# gateway.net
KiCad netlist of a schematic drawn in EAGLE
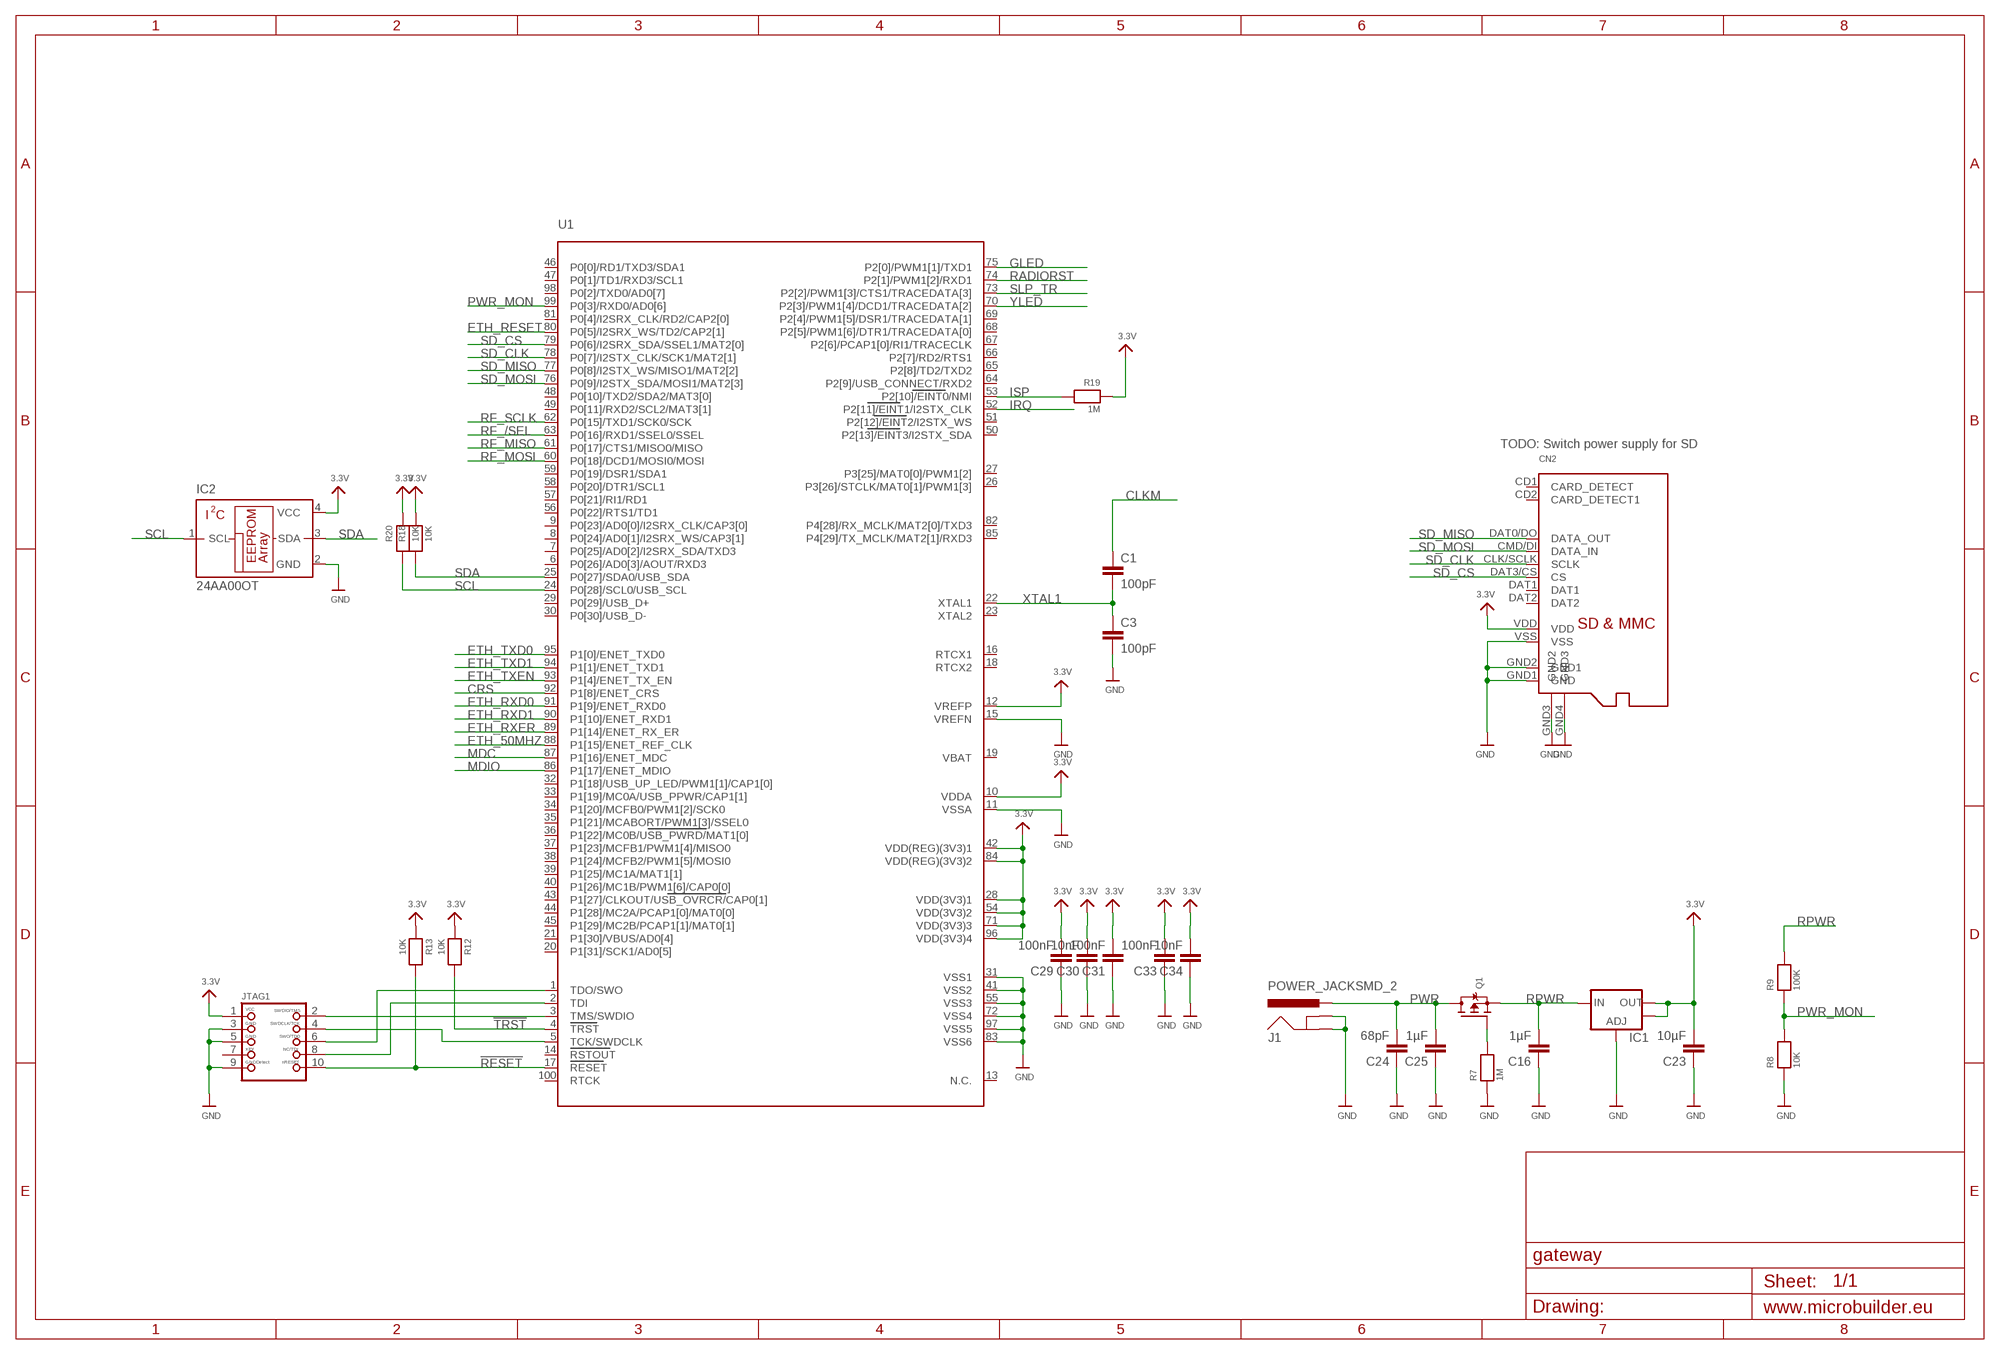
[diagram p0: schematic, sheet 1, part 1 of 2]
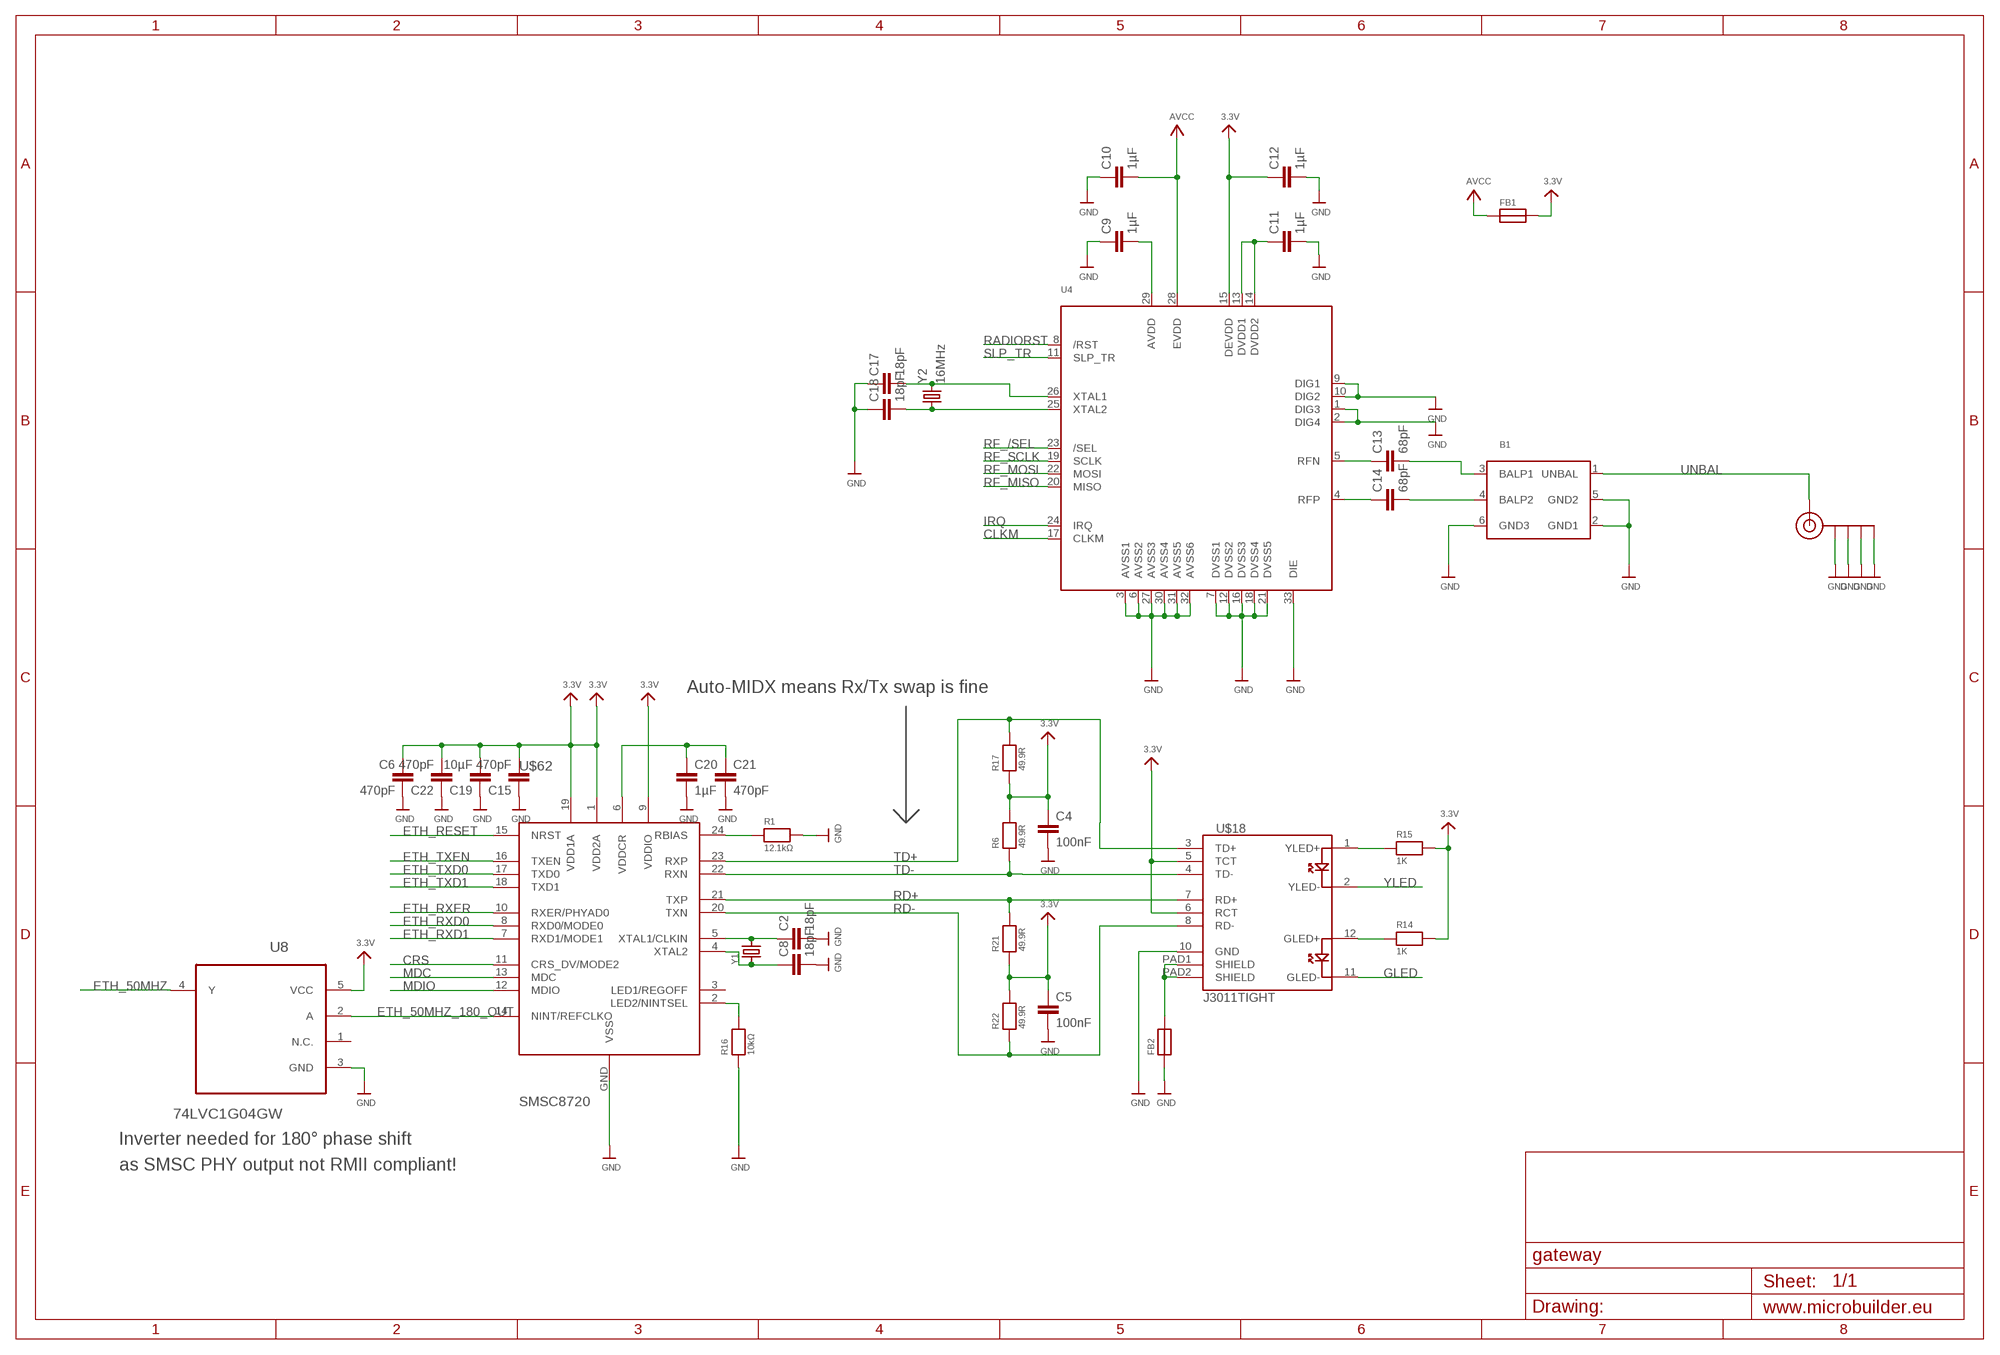
[diagram p1: schematic, sheet 1, part 2 of 2]

(export (version "E")
  (design (tool "Eeschema 10.0.6"))
  (components
    (comp (ref "B1")
      (value "BALUN+LP")
      (footprint "eagle-import:BALUN0805")
      (libsource (lib "eagle-import") (part "BALUN+LP"))
    )
    (comp (ref "C1")
      (value "100pF")
      (footprint "eagle-import:C0603K")
      (libsource (lib "eagle-import") (part "C-EUC0603K"))
    )
    (comp (ref "C2")
      (value "18pF")
      (footprint "eagle-import:C0603K")
      (libsource (lib "eagle-import") (part "C-EUC0603K"))
    )
    (comp (ref "C3")
      (value "100pF")
      (footprint "eagle-import:C0603K")
      (libsource (lib "eagle-import") (part "C-EUC0603K"))
    )
    (comp (ref "C4")
      (value "100nF")
      (footprint "eagle-import:C1206")
      (libsource (lib "eagle-import") (part "C-EUC1206"))
    )
    (comp (ref "C5")
      (value "100nF")
      (footprint "eagle-import:C1206")
      (libsource (lib "eagle-import") (part "C-EUC1206"))
    )
    (comp (ref "C6")
      (value "470pF")
      (footprint "eagle-import:C0603K")
      (libsource (lib "eagle-import") (part "C-EUC0603K"))
    )
    (comp (ref "C8")
      (value "18pF")
      (footprint "eagle-import:C0603K")
      (libsource (lib "eagle-import") (part "C-EUC0603K"))
    )
    (comp (ref "C9")
      (value "1µF")
      (footprint "eagle-import:C0603K")
      (libsource (lib "eagle-import") (part "C-EUC0603K"))
    )
    (comp (ref "C10")
      (value "1µF")
      (footprint "eagle-import:C0603K")
      (libsource (lib "eagle-import") (part "C-EUC0603K"))
    )
    (comp (ref "C11")
      (value "1µF")
      (footprint "eagle-import:C0603K")
      (libsource (lib "eagle-import") (part "C-EUC0603K"))
    )
    (comp (ref "C12")
      (value "1µF")
      (footprint "eagle-import:C0603K")
      (libsource (lib "eagle-import") (part "C-EUC0603K"))
    )
    (comp (ref "C13")
      (value "68pF")
      (footprint "eagle-import:C0603K")
      (libsource (lib "eagle-import") (part "C-EUC0603K"))
    )
    (comp (ref "C14")
      (value "68pF")
      (footprint "eagle-import:C0603K")
      (libsource (lib "eagle-import") (part "C-EUC0603K"))
    )
    (comp (ref "C15")
      (value "470pF")
      (footprint "eagle-import:C0603K")
      (libsource (lib "eagle-import") (part "C-EUC0603K"))
    )
    (comp (ref "C16")
      (value "1µF")
      (footprint "eagle-import:C0603K")
      (libsource (lib "eagle-import") (part "C-EUC0603K"))
    )
    (comp (ref "C17")
      (value "18pF")
      (footprint "eagle-import:C0603K")
      (libsource (lib "eagle-import") (part "C-EUC0603K"))
    )
    (comp (ref "C18")
      (value "18pF")
      (footprint "eagle-import:C0603K")
      (libsource (lib "eagle-import") (part "C-EUC0603K"))
    )
    (comp (ref "C19")
      (value "10µF")
      (footprint "eagle-import:C0603K")
      (libsource (lib "eagle-import") (part "C-EUC0603K"))
    )
    (comp (ref "C20")
      (value "1µF")
      (footprint "eagle-import:C0603K")
      (libsource (lib "eagle-import") (part "C-EUC0603K"))
    )
    (comp (ref "C21")
      (value "470pF")
      (footprint "eagle-import:C0603K")
      (libsource (lib "eagle-import") (part "C-EUC0603K"))
    )
    (comp (ref "C22")
      (value "470pF")
      (footprint "eagle-import:C0603K")
      (libsource (lib "eagle-import") (part "C-EUC0603K"))
    )
    (comp (ref "C23")
      (value "10µF")
      (footprint "eagle-import:C0603K")
      (libsource (lib "eagle-import") (part "C-EUC0603K"))
    )
    (comp (ref "C24")
      (value "68pF")
      (footprint "eagle-import:C0603K")
      (libsource (lib "eagle-import") (part "C-EUC0603K"))
    )
    (comp (ref "C25")
      (value "1µF")
      (footprint "eagle-import:C0603K")
      (libsource (lib "eagle-import") (part "C-EUC0603K"))
    )
    (comp (ref "C29")
      (value "100nF")
      (footprint "eagle-import:C0603K")
      (libsource (lib "eagle-import") (part "C-EUC0603K"))
    )
    (comp (ref "C30")
      (value "10nF")
      (footprint "eagle-import:C0603K")
      (libsource (lib "eagle-import") (part "C-EUC0603K"))
    )
    (comp (ref "C31")
      (value "100nF")
      (footprint "eagle-import:C0603K")
      (libsource (lib "eagle-import") (part "C-EUC0603K"))
    )
    (comp (ref "C33")
      (value "100nF")
      (footprint "eagle-import:C0603K")
      (libsource (lib "eagle-import") (part "C-EUC0603K"))
    )
    (comp (ref "C34")
      (value "10nF")
      (footprint "eagle-import:C0603K")
      (libsource (lib "eagle-import") (part "C-EUC0603K"))
    )
    (comp (ref "CN2")
      (value "MICROSDDM3B")
      (footprint "eagle-import:MICROSD_DM3B")
      (libsource (lib "eagle-import") (part "MICROSDDM3B"))
    )
    (comp (ref "FB1")
      (value "FERRITE")
      (footprint "eagle-import:0603")
      (libsource (lib "eagle-import") (part "FERRITE"))
    )
    (comp (ref "FB2")
      (value "FERRITE")
      (footprint "eagle-import:0603")
      (libsource (lib "eagle-import") (part "FERRITE"))
    )
    (comp (ref "IC1")
      (value "V_REG_LM1117SOT223")
      (footprint "eagle-import:SOT223")
      (libsource (lib "eagle-import") (part "V_REG_LM1117SOT223"))
    )
    (comp (ref "IC2")
      (value "24AA00OT")
      (footprint "eagle-import:SOT23-5L")
      (fields (field (name "MF") "MICROCHIP") (field (name "MPN") "24AA00T-I/OTG"))
      (libsource (lib "eagle-import") (part "2400OTAA"))
    )
    (comp (ref "J$1")
      (value "SMA_EDGE")
      (footprint "eagle-import:SMA-EDGE")
      (libsource (lib "eagle-import") (part "SMA_EDGE"))
    )
    (comp (ref "J1")
      (value "POWER_JACKSMD_2")
      (footprint "eagle-import:POWER_JACK_SMD_2")
      (libsource (lib "eagle-import") (part "POWER_JACKSMD_2"))
    )
    (comp (ref "JTAG1")
      (value "JTAG-CORTEXM3")
      (footprint "eagle-import:2X05_1.27MM_SMT")
      (libsource (lib "eagle-import") (part "JTAG-CORTEXM3"))
    )
    (comp (ref "Q1")
      (value "MOSFET-P")
      (footprint "eagle-import:SOT23-R")
      (libsource (lib "eagle-import") (part "MOSFET-P"))
    )
    (comp (ref "R1")
      (value "12.1kΩ")
      (footprint "eagle-import:0603-MINI")
      (libsource (lib "eagle-import") (part "RESISTOR0603MINI"))
    )
    (comp (ref "R6")
      (value "49.9R")
      (footprint "eagle-import:0603-MINI")
      (libsource (lib "eagle-import") (part "RESISTOR0603MINI"))
    )
    (comp (ref "R7")
      (value "1M")
      (footprint "eagle-import:0603-MINI")
      (libsource (lib "eagle-import") (part "RESISTOR0603MINI"))
    )
    (comp (ref "R8")
      (value "10K")
      (footprint "eagle-import:0603-MINI")
      (libsource (lib "eagle-import") (part "RESISTOR0603MINI"))
    )
    (comp (ref "R9")
      (value "100K")
      (footprint "eagle-import:0603-MINI")
      (libsource (lib "eagle-import") (part "RESISTOR0603MINI"))
    )
    (comp (ref "R12")
      (value "10K")
      (footprint "eagle-import:0603-MINI")
      (libsource (lib "eagle-import") (part "RESISTOR0603MINI"))
    )
    (comp (ref "R13")
      (value "10K")
      (footprint "eagle-import:0603-MINI")
      (libsource (lib "eagle-import") (part "RESISTOR0603MINI"))
    )
    (comp (ref "R14")
      (value "1K")
      (footprint "eagle-import:0603-MINI")
      (libsource (lib "eagle-import") (part "RESISTOR0603MINI"))
    )
    (comp (ref "R15")
      (value "1K")
      (footprint "eagle-import:0603-MINI")
      (libsource (lib "eagle-import") (part "RESISTOR0603MINI"))
    )
    (comp (ref "R16")
      (value "10kΩ")
      (footprint "eagle-import:0603-MINI")
      (libsource (lib "eagle-import") (part "RESISTOR0603MINI"))
    )
    (comp (ref "R17")
      (value "49.9R")
      (footprint "eagle-import:0603-MINI")
      (libsource (lib "eagle-import") (part "RESISTOR0603MINI"))
    )
    (comp (ref "R18")
      (value "10K")
      (footprint "eagle-import:0603-MINI")
      (libsource (lib "eagle-import") (part "RESISTOR0603MINI"))
    )
    (comp (ref "R19")
      (value "1M")
      (footprint "eagle-import:0603-MINI")
      (libsource (lib "eagle-import") (part "RESISTOR0603MINI"))
    )
    (comp (ref "R20")
      (value "10K")
      (footprint "eagle-import:0603-MINI")
      (libsource (lib "eagle-import") (part "RESISTOR0603MINI"))
    )
    (comp (ref "R21")
      (value "49.9R")
      (footprint "eagle-import:0603-MINI")
      (libsource (lib "eagle-import") (part "RESISTOR0603MINI"))
    )
    (comp (ref "R22")
      (value "49.9R")
      (footprint "eagle-import:0603-MINI")
      (libsource (lib "eagle-import") (part "RESISTOR0603MINI"))
    )
    (comp (ref "U$18")
      (value "J3011TIGHT")
      (footprint "eagle-import:J3011_TIGHT")
      (libsource (lib "eagle-import") (part "J3011TIGHT"))
    )
    (comp (ref "U$62")
      (value "SMSC8720")
      (footprint "eagle-import:QFN24_SMSC8720")
      (libsource (lib "eagle-import") (part "SMSC8720"))
    )
    (comp (ref "U1")
      (value "LPC1768")
      (footprint "eagle-import:LQFP100")
      (libsource (lib "eagle-import") (part "LPC1768"))
    )
    (comp (ref "U4")
      (value "AT86RF212")
      (footprint "eagle-import:32QN2")
      (libsource (lib "eagle-import") (part "AT86RF212"))
    )
    (comp (ref "U8")
      (value "74LVC1G04GW")
      (footprint "eagle-import:SOT65P210X110-5N")
      (libsource (lib "eagle-import") (part "74LVC1G04GW"))
    )
    (comp (ref "Y1")
      (value "CRYSTALTHIN32K")
      (footprint "eagle-import:CRYSTAL_4.9X1.8")
      (libsource (lib "eagle-import") (part "CRYSTALTHIN32K"))
    )
    (comp (ref "Y2")
      (value "16MHz")
      (footprint "eagle-import:CRYSTAL-SMD-5X3")
      (libsource (lib "eagle-import") (part "CRYSTAL5X3"))
    )
  )
  (nets
    (net (code "1") (name "/CLKM") (class "Default")
      (node (ref "C1") (pin "1") (pinfunction "1_1") (pintype "passive"))
      (node (ref "U4") (pin "17") (pinfunction "CLKM_17") (pintype "bidirectional"))
    )
    (net (code "2") (name "/CRS") (class "Default")
      (node (ref "U$62") (pin "11") (pinfunction "CRS_DV/MODE2_11") (pintype "bidirectional"))
      (node (ref "U1") (pin "92") (pinfunction "P1[8]/ENET_CRS_92") (pintype "bidirectional"))
    )
    (net (code "3") (name "/ETH_50MHZ") (class "Default")
      (node (ref "U1") (pin "88") (pinfunction "P1[15]/ENET_REF_CLK_88") (pintype "bidirectional"))
      (node (ref "U8") (pin "4") (pinfunction "Y_4") (pintype "output"))
    )
    (net (code "4") (name "/ETH_50MHZ_180_OUT") (class "Default")
      (node (ref "U$62") (pin "14") (pinfunction "NINT/REFCLKO_14") (pintype "bidirectional"))
      (node (ref "U8") (pin "2") (pinfunction "A_2") (pintype "input"))
    )
    (net (code "5") (name "/ETH_RESET") (class "Default")
      (node (ref "U$62") (pin "15") (pinfunction "NRST_15") (pintype "bidirectional"))
      (node (ref "U1") (pin "80") (pinfunction "P0[5]/I2SRX_WS/TD2/CAP2[1]_80") (pintype "bidirectional"))
    )
    (net (code "6") (name "/ETH_RXD0") (class "Default")
      (node (ref "U$62") (pin "8") (pinfunction "RXD0/MODE0_8") (pintype "bidirectional"))
      (node (ref "U1") (pin "91") (pinfunction "P1[9]/ENET_RXD0_91") (pintype "bidirectional"))
    )
    (net (code "7") (name "/ETH_RXD1") (class "Default")
      (node (ref "U$62") (pin "7") (pinfunction "RXD1/MODE1_7") (pintype "bidirectional"))
      (node (ref "U1") (pin "90") (pinfunction "P1[10]/ENET_RXD1_90") (pintype "bidirectional"))
    )
    (net (code "8") (name "/ETH_RXER") (class "Default")
      (node (ref "U$62") (pin "10") (pinfunction "RXER/PHYAD0_10") (pintype "bidirectional"))
      (node (ref "U1") (pin "89") (pinfunction "P1[14]/ENET_RX_ER_89") (pintype "bidirectional"))
    )
    (net (code "9") (name "/ETH_TXD0") (class "Default")
      (node (ref "U$62") (pin "17") (pinfunction "TXD0_17") (pintype "bidirectional"))
      (node (ref "U1") (pin "95") (pinfunction "P1[0]/ENET_TXD0_95") (pintype "bidirectional"))
    )
    (net (code "10") (name "/ETH_TXD1") (class "Default")
      (node (ref "U$62") (pin "18") (pinfunction "TXD1_18") (pintype "bidirectional"))
      (node (ref "U1") (pin "94") (pinfunction "P1[1]/ENET_TXD1_94") (pintype "bidirectional"))
    )
    (net (code "11") (name "/ETH_TXEN") (class "Default")
      (node (ref "U$62") (pin "16") (pinfunction "TXEN_16") (pintype "bidirectional"))
      (node (ref "U1") (pin "93") (pinfunction "P1[4]/ENET_TX_EN_93") (pintype "bidirectional"))
    )
    (net (code "12") (name "/GLED") (class "Default")
      (node (ref "U$18") (pin "11") (pinfunction "GLED-_11") (pintype "bidirectional"))
      (node (ref "U1") (pin "75") (pinfunction "P2[0]/PWM1[1]/TXD1_75") (pintype "bidirectional"))
    )
    (net (code "13") (name "/IRQ") (class "Default")
      (node (ref "U1") (pin "52") (pinfunction "P2[11]/EINT1/I2STX_CLK_52") (pintype "bidirectional"))
      (node (ref "U4") (pin "24") (pinfunction "IRQ_24") (pintype "bidirectional"))
    )
    (net (code "14") (name "/ISP") (class "Default")
      (node (ref "R19") (pin "2") (pinfunction "2_2") (pintype "passive"))
      (node (ref "U1") (pin "53") (pinfunction "P2[10]/EINT0/NMI_53") (pintype "bidirectional"))
    )
    (net (code "15") (name "/MDC") (class "Default")
      (node (ref "U$62") (pin "13") (pinfunction "MDC_13") (pintype "bidirectional"))
      (node (ref "U1") (pin "87") (pinfunction "P1[16]/ENET_MDC_87") (pintype "bidirectional"))
    )
    (net (code "16") (name "/MDIO") (class "Default")
      (node (ref "U$62") (pin "12") (pinfunction "MDIO_12") (pintype "bidirectional"))
      (node (ref "U1") (pin "86") (pinfunction "P1[17]/ENET_MDIO_86") (pintype "bidirectional"))
    )
    (net (code "17") (name "/PWR") (class "Default")
      (node (ref "C24") (pin "2") (pinfunction "2_2") (pintype "passive"))
      (node (ref "C25") (pin "2") (pinfunction "2_2") (pintype "passive"))
      (node (ref "J1") (pin "VIN0") (pinfunction "PWR_VIN0") (pintype "bidirectional"))
      (node (ref "Q1") (pin "3") (pinfunction "D_3") (pintype "passive"))
    )
    (net (code "18") (name "/PWR_MON") (class "Default")
      (node (ref "R8") (pin "2") (pinfunction "2_2") (pintype "passive"))
      (node (ref "R9") (pin "1") (pinfunction "1_1") (pintype "passive"))
      (node (ref "U1") (pin "99") (pinfunction "P0[3]/RXD0/AD0[6]_99") (pintype "bidirectional"))
    )
    (net (code "19") (name "/RADIORST") (class "Default")
      (node (ref "U1") (pin "74") (pinfunction "P2[1]/PWM1[2]/RXD1_74") (pintype "bidirectional"))
      (node (ref "U4") (pin "8") (pinfunction "/RST_8") (pintype "bidirectional"))
    )
    (net (code "20") (name "/RD+") (class "Default")
      (node (ref "R21") (pin "2") (pinfunction "2_2") (pintype "passive"))
      (node (ref "U$18") (pin "7") (pinfunction "RD+_7") (pintype "bidirectional"))
      (node (ref "U$62") (pin "21") (pinfunction "TXP_21") (pintype "bidirectional"))
    )
    (net (code "21") (name "/RD-") (class "Default")
      (node (ref "R22") (pin "1") (pinfunction "1_1") (pintype "passive"))
      (node (ref "U$18") (pin "8") (pinfunction "RD-_8") (pintype "bidirectional"))
      (node (ref "U$62") (pin "20") (pinfunction "TXN_20") (pintype "bidirectional"))
    )
    (net (code "22") (name "/RF_MISO") (class "Default")
      (node (ref "U1") (pin "61") (pinfunction "P0[17]/CTS1/MISO0/MISO_61") (pintype "bidirectional"))
      (node (ref "U4") (pin "20") (pinfunction "MISO_20") (pintype "bidirectional"))
    )
    (net (code "23") (name "/RF_MOSI") (class "Default")
      (node (ref "U1") (pin "60") (pinfunction "P0[18]/DCD1/MOSI0/MOSI_60") (pintype "bidirectional"))
      (node (ref "U4") (pin "22") (pinfunction "MOSI_22") (pintype "bidirectional"))
    )
    (net (code "24") (name "/RF_SCLK") (class "Default")
      (node (ref "U1") (pin "62") (pinfunction "P0[15]/TXD1/SCK0/SCK_62") (pintype "bidirectional"))
      (node (ref "U4") (pin "19") (pinfunction "SCLK_19") (pintype "bidirectional"))
    )
    (net (code "25") (name "/RF_{slash}SEL") (class "Default")
      (node (ref "U1") (pin "63") (pinfunction "P0[16]/RXD1/SSEL0/SSEL_63") (pintype "bidirectional"))
      (node (ref "U4") (pin "23") (pinfunction "/SEL_23") (pintype "bidirectional"))
    )
    (net (code "26") (name "/RPWR") (class "Default")
      (node (ref "C16") (pin "2") (pinfunction "2_2") (pintype "passive"))
      (node (ref "IC1") (pin "3") (pinfunction "IN_3") (pintype "input"))
      (node (ref "Q1") (pin "2") (pinfunction "S_2") (pintype "passive"))
      (node (ref "R9") (pin "2") (pinfunction "2_2") (pintype "passive"))
    )
    (net (code "27") (name "/SCL") (class "Default")
      (node (ref "IC2") (pin "1") (pinfunction "SCL_1") (pintype "input"))
      (node (ref "R20") (pin "2") (pinfunction "2_2") (pintype "passive"))
      (node (ref "U1") (pin "24") (pinfunction "P0[28]/SCL0/USB_SCL_24") (pintype "bidirectional"))
    )
    (net (code "28") (name "/SDA") (class "Default")
      (node (ref "IC2") (pin "3") (pinfunction "SDA_3") (pintype "bidirectional"))
      (node (ref "R18") (pin "2") (pinfunction "2_2") (pintype "passive"))
      (node (ref "U1") (pin "25") (pinfunction "P0[27]/SDA0/USB_SDA_25") (pintype "bidirectional"))
    )
    (net (code "29") (name "/SD_CLK") (class "Default")
      (node (ref "CN2") (pin "CLK/SCLK") (pinfunction "SCLK_CLK/SCLK") (pintype "input"))
      (node (ref "U1") (pin "78") (pinfunction "P0[7]/I2STX_CLK/SCK1/MAT2[1]_78") (pintype "bidirectional"))
    )
    (net (code "30") (name "/SD_CS") (class "Default")
      (node (ref "CN2") (pin "DAT3/CS") (pinfunction "CS_DAT3/CS") (pintype "input"))
      (node (ref "U1") (pin "79") (pinfunction "P0[6]/I2SRX_SDA/SSEL1/MAT2[0]_79") (pintype "bidirectional"))
    )
    (net (code "31") (name "/SD_MISO") (class "Default")
      (node (ref "CN2") (pin "DAT0/DO") (pinfunction "DATA_OUT_DAT0/DO") (pintype "output"))
      (node (ref "U1") (pin "77") (pinfunction "P0[8]/I2STX_WS/MISO1/MAT2[2]_77") (pintype "bidirectional"))
    )
    (net (code "32") (name "/SD_MOSI") (class "Default")
      (node (ref "CN2") (pin "CMD/DI") (pinfunction "DATA_IN_CMD/DI") (pintype "input"))
      (node (ref "U1") (pin "76") (pinfunction "P0[9]/I2STX_SDA/MOSI1/MAT2[3]_76") (pintype "bidirectional"))
    )
    (net (code "33") (name "/SLP_TR") (class "Default")
      (node (ref "U1") (pin "73") (pinfunction "P2[2]/PWM1[3]/CTS1/TRACEDATA[3]_73") (pintype "bidirectional"))
      (node (ref "U4") (pin "11") (pinfunction "SLP_TR_11") (pintype "bidirectional"))
    )
    (net (code "34") (name "/TD+") (class "Default")
      (node (ref "R17") (pin "2") (pinfunction "2_2") (pintype "passive"))
      (node (ref "U$18") (pin "3") (pinfunction "TD+_3") (pintype "bidirectional"))
      (node (ref "U$62") (pin "23") (pinfunction "RXP_23") (pintype "bidirectional"))
    )
    (net (code "35") (name "/TD-") (class "Default")
      (node (ref "R6") (pin "1") (pinfunction "1_1") (pintype "passive"))
      (node (ref "U$18") (pin "4") (pinfunction "TD-_4") (pintype "bidirectional"))
      (node (ref "U$62") (pin "22") (pinfunction "RXN_22") (pintype "bidirectional"))
    )
    (net (code "36") (name "/UNBAL") (class "Default")
      (node (ref "B1") (pin "1") (pinfunction "UNBAL_1") (pintype "bidirectional"))
      (node (ref "J$1") (pin "SIG") (pinfunction "SIGNAL_SIG") (pintype "bidirectional"))
    )
    (net (code "37") (name "/VBAT") (class "Default")
      (node (ref "U1") (pin "19") (pinfunction "VBAT_19") (pintype "power_in"))
    )
    (net (code "38") (name "/XTAL1") (class "Default")
      (node (ref "C1") (pin "2") (pinfunction "2_2") (pintype "passive"))
      (node (ref "C3") (pin "1") (pinfunction "1_1") (pintype "passive"))
      (node (ref "U1") (pin "22") (pinfunction "XTAL1_22") (pintype "bidirectional"))
    )
    (net (code "39") (name "/YLED") (class "Default")
      (node (ref "U$18") (pin "2") (pinfunction "YLED-_2") (pintype "bidirectional"))
      (node (ref "U1") (pin "70") (pinfunction "P2[3]/PWM1[4]/DCD1/TRACEDATA[2]_70") (pintype "bidirectional"))
    )
    (net (code "40") (name "/~{RESET}") (class "Default")
      (node (ref "JTAG1") (pin "10") (pinfunction "10_10") (pintype "passive"))
      (node (ref "R13") (pin "2") (pinfunction "2_2") (pintype "passive"))
      (node (ref "U1") (pin "17") (pinfunction "RESET_17") (pintype "bidirectional"))
    )
    (net (code "41") (name "/~{TRST}") (class "Default")
      (node (ref "R12") (pin "2") (pinfunction "2_2") (pintype "passive"))
      (node (ref "U1") (pin "4") (pinfunction "TRST_4") (pintype "bidirectional"))
    )
    (net (code "42") (name "3.3V") (class "Default")
      (node (ref "C12") (pin "1") (pinfunction "1_1") (pintype "passive"))
      (node (ref "C15") (pin "2") (pinfunction "2_2") (pintype "passive"))
      (node (ref "C19") (pin "2") (pinfunction "2_2") (pintype "passive"))
      (node (ref "C22") (pin "2") (pinfunction "2_2") (pintype "passive"))
      (node (ref "C23") (pin "2") (pinfunction "2_2") (pintype "passive"))
      (node (ref "C29") (pin "2") (pinfunction "2_2") (pintype "passive"))
      (node (ref "C30") (pin "2") (pinfunction "2_2") (pintype "passive"))
      (node (ref "C31") (pin "2") (pinfunction "2_2") (pintype "passive"))
      (node (ref "C33") (pin "2") (pinfunction "2_2") (pintype "passive"))
      (node (ref "C34") (pin "2") (pinfunction "2_2") (pintype "passive"))
      (node (ref "C4") (pin "1") (pinfunction "1_1") (pintype "passive"))
      (node (ref "C5") (pin "1") (pinfunction "1_1") (pintype "passive"))
      (node (ref "C6") (pin "1") (pinfunction "1_1") (pintype "passive"))
      (node (ref "CN2") (pin "VDD") (pinfunction "VDD_VDD") (pintype "power_in"))
      (node (ref "FB1") (pin "2") (pinfunction "P$2_2") (pintype "bidirectional"))
      (node (ref "IC1") (pin "2") (pinfunction "OUT_2") (pintype "output"))
      (node (ref "IC1") (pin "4") (pinfunction "OUT_4") (pintype "output"))
      (node (ref "IC2") (pin "4") (pinfunction "VCC_4") (pintype "power_in"))
      (node (ref "JTAG1") (pin "1") (pinfunction "1_1") (pintype "passive"))
      (node (ref "R12") (pin "1") (pinfunction "1_1") (pintype "passive"))
      (node (ref "R13") (pin "1") (pinfunction "1_1") (pintype "passive"))
      (node (ref "R14") (pin "2") (pinfunction "2_2") (pintype "passive"))
      (node (ref "R15") (pin "2") (pinfunction "2_2") (pintype "passive"))
      (node (ref "R17") (pin "1") (pinfunction "1_1") (pintype "passive"))
      (node (ref "R18") (pin "1") (pinfunction "1_1") (pintype "passive"))
      (node (ref "R19") (pin "1") (pinfunction "1_1") (pintype "passive"))
      (node (ref "R20") (pin "1") (pinfunction "1_1") (pintype "passive"))
      (node (ref "R21") (pin "1") (pinfunction "1_1") (pintype "passive"))
      (node (ref "R22") (pin "2") (pinfunction "2_2") (pintype "passive"))
      (node (ref "R6") (pin "2") (pinfunction "2_2") (pintype "passive"))
      (node (ref "U$18") (pin "5") (pinfunction "TCT_5") (pintype "bidirectional"))
      (node (ref "U$18") (pin "6") (pinfunction "RCT_6") (pintype "bidirectional"))
      (node (ref "U$62") (pin "1") (pinfunction "VDD2A_1") (pintype "bidirectional"))
      (node (ref "U$62") (pin "19") (pinfunction "VDD1A_19") (pintype "bidirectional"))
      (node (ref "U$62") (pin "9") (pinfunction "VDDIO_9") (pintype "bidirectional"))
      (node (ref "U1") (pin "10") (pinfunction "VDDA_10") (pintype "power_in"))
      (node (ref "U1") (pin "12") (pinfunction "VREFP_12") (pintype "power_in"))
      (node (ref "U1") (pin "28") (pinfunction "VDD(3V3)1_28") (pintype "power_in"))
      (node (ref "U1") (pin "42") (pinfunction "VDD(REG)(3V3)1_42") (pintype "power_in"))
      (node (ref "U1") (pin "54") (pinfunction "VDD(3V3)2_54") (pintype "power_in"))
      (node (ref "U1") (pin "71") (pinfunction "VDD(3V3)3_71") (pintype "power_in"))
      (node (ref "U1") (pin "84") (pinfunction "VDD(REG)(3V3)2_84") (pintype "power_in"))
      (node (ref "U1") (pin "96") (pinfunction "VDD(3V3)4_96") (pintype "power_in"))
      (node (ref "U4") (pin "15") (pinfunction "DEVDD_15") (pintype "bidirectional"))
      (node (ref "U8") (pin "5") (pinfunction "VCC_5") (pintype "power_in"))
    )
    (net (code "43") (name "AVCC") (class "Default")
      (node (ref "C10") (pin "2") (pinfunction "2_2") (pintype "passive"))
      (node (ref "FB1") (pin "1") (pinfunction "P$1_1") (pintype "bidirectional"))
      (node (ref "U4") (pin "28") (pinfunction "EVDD_28") (pintype "bidirectional"))
    )
    (net (code "44") (name "GND") (class "Default")
      (node (ref "B1") (pin "2") (pinfunction "GND1_2") (pintype "bidirectional"))
      (node (ref "B1") (pin "5") (pinfunction "GND2_5") (pintype "bidirectional"))
      (node (ref "B1") (pin "6") (pinfunction "GND3_6") (pintype "bidirectional"))
      (node (ref "C10") (pin "1") (pinfunction "1_1") (pintype "passive"))
      (node (ref "C11") (pin "2") (pinfunction "2_2") (pintype "passive"))
      (node (ref "C12") (pin "2") (pinfunction "2_2") (pintype "passive"))
      (node (ref "C15") (pin "1") (pinfunction "1_1") (pintype "passive"))
      (node (ref "C16") (pin "1") (pinfunction "1_1") (pintype "passive"))
      (node (ref "C17") (pin "1") (pinfunction "1_1") (pintype "passive"))
      (node (ref "C18") (pin "1") (pinfunction "1_1") (pintype "passive"))
      (node (ref "C19") (pin "1") (pinfunction "1_1") (pintype "passive"))
      (node (ref "C2") (pin "2") (pinfunction "2_2") (pintype "passive"))
      (node (ref "C20") (pin "2") (pinfunction "2_2") (pintype "passive"))
      (node (ref "C21") (pin "2") (pinfunction "2_2") (pintype "passive"))
      (node (ref "C22") (pin "1") (pinfunction "1_1") (pintype "passive"))
      (node (ref "C23") (pin "1") (pinfunction "1_1") (pintype "passive"))
      (node (ref "C24") (pin "1") (pinfunction "1_1") (pintype "passive"))
      (node (ref "C25") (pin "1") (pinfunction "1_1") (pintype "passive"))
      (node (ref "C29") (pin "1") (pinfunction "1_1") (pintype "passive"))
      (node (ref "C3") (pin "2") (pinfunction "2_2") (pintype "passive"))
      (node (ref "C30") (pin "1") (pinfunction "1_1") (pintype "passive"))
      (node (ref "C31") (pin "1") (pinfunction "1_1") (pintype "passive"))
      (node (ref "C33") (pin "1") (pinfunction "1_1") (pintype "passive"))
      (node (ref "C34") (pin "1") (pinfunction "1_1") (pintype "passive"))
      (node (ref "C4") (pin "2") (pinfunction "2_2") (pintype "passive"))
      (node (ref "C5") (pin "2") (pinfunction "2_2") (pintype "passive"))
      (node (ref "C6") (pin "2") (pinfunction "2_2") (pintype "passive"))
      (node (ref "C8") (pin "2") (pinfunction "2_2") (pintype "passive"))
      (node (ref "C9") (pin "1") (pinfunction "1_1") (pintype "passive"))
      (node (ref "CN2") (pin "GND1") (pinfunction "GND_GND1") (pintype "power_in"))
      (node (ref "CN2") (pin "GND2") (pinfunction "GND1_GND2") (pintype "power_in"))
      (node (ref "CN2") (pin "GND3") (pinfunction "GND2_GND3") (pintype "bidirectional"))
      (node (ref "CN2") (pin "GND4") (pinfunction "GND3_GND4") (pintype "bidirectional"))
      (node (ref "CN2") (pin "VSS") (pinfunction "VSS_VSS") (pintype "power_in"))
      (node (ref "FB2") (pin "1") (pinfunction "P$1_1") (pintype "bidirectional"))
      (node (ref "IC1") (pin "1") (pinfunction "ADJ_1") (pintype "input"))
      (node (ref "IC2") (pin "2") (pinfunction "GND_2") (pintype "power_in"))
      (node (ref "J$1") (pin "GND@0") (pinfunction "GND_GND@0") (pintype "bidirectional"))
      (node (ref "J$1") (pin "GND@1") (pinfunction "GND_GND@1") (pintype "bidirectional"))
      (node (ref "J$1") (pin "GND@2") (pinfunction "GND_GND@2") (pintype "bidirectional"))
      (node (ref "J$1") (pin "GND@3") (pinfunction "GND_GND@3") (pintype "bidirectional"))
      (node (ref "J1") (pin "GND") (pinfunction "GNDBREAK_GND") (pintype "bidirectional"))
      (node (ref "J1") (pin "P$4") (pinfunction "GND_P$4") (pintype "bidirectional"))
      (node (ref "JTAG1") (pin "3") (pinfunction "3_3") (pintype "passive"))
      (node (ref "JTAG1") (pin "5") (pinfunction "5_5") (pintype "passive"))
      (node (ref "JTAG1") (pin "9") (pinfunction "9_9") (pintype "passive"))
      (node (ref "R1") (pin "2") (pinfunction "2_2") (pintype "passive"))
      (node (ref "R16") (pin "1") (pinfunction "1_1") (pintype "passive"))
      (node (ref "R7") (pin "1") (pinfunction "1_1") (pintype "passive"))
      (node (ref "R8") (pin "1") (pinfunction "1_1") (pintype "passive"))
      (node (ref "U$18") (pin "10") (pinfunction "GND_10") (pintype "bidirectional"))
      (node (ref "U$62") (pin "GND") (pinfunction "VSS_GND") (pintype "bidirectional"))
      (node (ref "U1") (pin "11") (pinfunction "VSSA_11") (pintype "power_in"))
      (node (ref "U1") (pin "15") (pinfunction "VREFN_15") (pintype "power_in"))
      (node (ref "U1") (pin "31") (pinfunction "VSS1_31") (pintype "power_in"))
      (node (ref "U1") (pin "41") (pinfunction "VSS2_41") (pintype "power_in"))
      (node (ref "U1") (pin "55") (pinfunction "VSS3_55") (pintype "power_in"))
      (node (ref "U1") (pin "72") (pinfunction "VSS4_72") (pintype "power_in"))
      (node (ref "U1") (pin "83") (pinfunction "VSS6_83") (pintype "power_in"))
      (node (ref "U1") (pin "97") (pinfunction "VSS5_97") (pintype "power_in"))
      (node (ref "U4") (pin "1") (pinfunction "DIG3_1") (pintype "bidirectional"))
      (node (ref "U4") (pin "10") (pinfunction "DIG2_10") (pintype "bidirectional"))
      (node (ref "U4") (pin "12") (pinfunction "DVSS2_12") (pintype "bidirectional"))
      (node (ref "U4") (pin "16") (pinfunction "DVSS3_16") (pintype "bidirectional"))
      (node (ref "U4") (pin "18") (pinfunction "DVSS4_18") (pintype "bidirectional"))
      (node (ref "U4") (pin "2") (pinfunction "DIG4_2") (pintype "bidirectional"))
      (node (ref "U4") (pin "21") (pinfunction "DVSS5_21") (pintype "bidirectional"))
      (node (ref "U4") (pin "27") (pinfunction "AVSS3_27") (pintype "bidirectional"))
      (node (ref "U4") (pin "3") (pinfunction "AVSS1_3") (pintype "bidirectional"))
      (node (ref "U4") (pin "30") (pinfunction "AVSS4_30") (pintype "bidirectional"))
      (node (ref "U4") (pin "31") (pinfunction "AVSS5_31") (pintype "bidirectional"))
      (node (ref "U4") (pin "32") (pinfunction "AVSS6_32") (pintype "bidirectional"))
      (node (ref "U4") (pin "33") (pinfunction "DIE_33") (pintype "bidirectional"))
      (node (ref "U4") (pin "6") (pinfunction "AVSS2_6") (pintype "bidirectional"))
      (node (ref "U4") (pin "7") (pinfunction "DVSS1_7") (pintype "bidirectional"))
      (node (ref "U4") (pin "9") (pinfunction "DIG1_9") (pintype "bidirectional"))
      (node (ref "U8") (pin "3") (pinfunction "GND_3") (pintype "passive"))
    )
    (net (code "45") (name "Net-(B1-BALP1)") (class "Default")
      (node (ref "B1") (pin "3") (pinfunction "BALP1_3") (pintype "bidirectional"))
      (node (ref "C13") (pin "2") (pinfunction "2_2") (pintype "passive"))
    )
    (net (code "46") (name "Net-(B1-BALP2)") (class "Default")
      (node (ref "B1") (pin "4") (pinfunction "BALP2_4") (pintype "bidirectional"))
      (node (ref "C14") (pin "2") (pinfunction "2_2") (pintype "passive"))
    )
    (net (code "47") (name "Net-(FB2-P$2)") (class "Default")
      (node (ref "FB2") (pin "2") (pinfunction "P$2_2") (pintype "bidirectional"))
      (node (ref "U$18") (pin "PAD1") (pinfunction "SHIELD_PAD1") (pintype "bidirectional"))
      (node (ref "U$18") (pin "PAD2") (pinfunction "SHIELD_PAD2") (pintype "bidirectional"))
    )
    (net (code "48") (name "Net-(Q1-G)") (class "Default")
      (node (ref "Q1") (pin "1") (pinfunction "G_1") (pintype "passive"))
      (node (ref "R7") (pin "2") (pinfunction "2_2") (pintype "passive"))
    )
    (net (code "49") (name "Net-(U$18-GLED+)") (class "Default")
      (node (ref "R14") (pin "1") (pinfunction "1_1") (pintype "passive"))
      (node (ref "U$18") (pin "12") (pinfunction "GLED+_12") (pintype "bidirectional"))
    )
    (net (code "50") (name "Net-(U$18-YLED+)") (class "Default")
      (node (ref "R15") (pin "1") (pinfunction "1_1") (pintype "passive"))
      (node (ref "U$18") (pin "1") (pinfunction "YLED+_1") (pintype "bidirectional"))
    )
    (net (code "51") (name "Net-(U$62-LED2{slash}NINTSEL)") (class "Default")
      (node (ref "R16") (pin "2") (pinfunction "2_2") (pintype "passive"))
      (node (ref "U$62") (pin "2") (pinfunction "LED2/NINTSEL_2") (pintype "bidirectional"))
    )
    (net (code "52") (name "Net-(U$62-RBIAS)") (class "Default")
      (node (ref "R1") (pin "1") (pinfunction "1_1") (pintype "passive"))
      (node (ref "U$62") (pin "24") (pinfunction "RBIAS_24") (pintype "bidirectional"))
    )
    (net (code "53") (name "Net-(U$62-VDDCR)") (class "Default")
      (node (ref "C20") (pin "1") (pinfunction "1_1") (pintype "passive"))
      (node (ref "C21") (pin "1") (pinfunction "1_1") (pintype "passive"))
      (node (ref "U$62") (pin "6") (pinfunction "VDDCR_6") (pintype "bidirectional"))
    )
    (net (code "54") (name "Net-(U$62-XTAL1{slash}CLKIN)") (class "Default")
      (node (ref "C2") (pin "1") (pinfunction "1_1") (pintype "passive"))
      (node (ref "U$62") (pin "5") (pinfunction "XTAL1/CLKIN_5") (pintype "bidirectional"))
      (node (ref "Y1") (pin "2") (pinfunction "2_2") (pintype "passive"))
    )
    (net (code "55") (name "Net-(U$62-XTAL2)") (class "Default")
      (node (ref "C8") (pin "1") (pinfunction "1_1") (pintype "passive"))
      (node (ref "U$62") (pin "4") (pinfunction "XTAL2_4") (pintype "bidirectional"))
      (node (ref "Y1") (pin "1") (pinfunction "1_1") (pintype "passive"))
    )
    (net (code "56") (name "Net-(U1-TCK{slash}SWDCLK)") (class "Default")
      (node (ref "JTAG1") (pin "4") (pinfunction "4_4") (pintype "passive"))
      (node (ref "U1") (pin "5") (pinfunction "TCK/SWDCLK_5") (pintype "bidirectional"))
    )
    (net (code "57") (name "Net-(U1-TDI)") (class "Default")
      (node (ref "JTAG1") (pin "8") (pinfunction "8_8") (pintype "passive"))
      (node (ref "U1") (pin "2") (pinfunction "TDI_2") (pintype "bidirectional"))
    )
    (net (code "58") (name "Net-(U1-TDO{slash}SWO)") (class "Default")
      (node (ref "JTAG1") (pin "6") (pinfunction "6_6") (pintype "passive"))
      (node (ref "U1") (pin "1") (pinfunction "TDO/SWO_1") (pintype "bidirectional"))
    )
    (net (code "59") (name "Net-(U1-TMS{slash}SWDIO)") (class "Default")
      (node (ref "JTAG1") (pin "2") (pinfunction "2_2") (pintype "passive"))
      (node (ref "U1") (pin "3") (pinfunction "TMS/SWDIO_3") (pintype "bidirectional"))
    )
    (net (code "60") (name "Net-(U4-AVDD)") (class "Default")
      (node (ref "C9") (pin "2") (pinfunction "2_2") (pintype "passive"))
      (node (ref "U4") (pin "29") (pinfunction "AVDD_29") (pintype "bidirectional"))
    )
    (net (code "61") (name "Net-(U4-DVDD1)") (class "Default")
      (node (ref "C11") (pin "1") (pinfunction "1_1") (pintype "passive"))
      (node (ref "U4") (pin "13") (pinfunction "DVDD1_13") (pintype "bidirectional"))
      (node (ref "U4") (pin "14") (pinfunction "DVDD2_14") (pintype "bidirectional"))
    )
    (net (code "62") (name "Net-(U4-RFN)") (class "Default")
      (node (ref "C13") (pin "1") (pinfunction "1_1") (pintype "passive"))
      (node (ref "U4") (pin "5") (pinfunction "RFN_5") (pintype "bidirectional"))
    )
    (net (code "63") (name "Net-(U4-RFP)") (class "Default")
      (node (ref "C14") (pin "1") (pinfunction "1_1") (pintype "passive"))
      (node (ref "U4") (pin "4") (pinfunction "RFP_4") (pintype "bidirectional"))
    )
    (net (code "64") (name "Net-(U4-XTAL1)") (class "Default")
      (node (ref "C17") (pin "2") (pinfunction "2_2") (pintype "passive"))
      (node (ref "U4") (pin "26") (pinfunction "XTAL1_26") (pintype "bidirectional"))
      (node (ref "Y2") (pin "3") (pinfunction "2_3") (pintype "passive"))
    )
    (net (code "65") (name "Net-(U4-XTAL2)") (class "Default")
      (node (ref "C18") (pin "2") (pinfunction "2_2") (pintype "passive"))
      (node (ref "U4") (pin "25") (pinfunction "XTAL2_25") (pintype "bidirectional"))
      (node (ref "Y2") (pin "1") (pinfunction "1_1") (pintype "passive"))
    )
    (net (code "66") (name "unconnected-(CN2-CARD_DETECT-PadCD1)") (class "Default")
      (node (ref "CN2") (pin "CD1") (pinfunction "CARD_DETECT_CD1") (pintype "passive"))
    )
    (net (code "67") (name "unconnected-(CN2-CARD_DETECT1-PadCD2)") (class "Default")
      (node (ref "CN2") (pin "CD2") (pinfunction "CARD_DETECT1_CD2") (pintype "passive"))
    )
    (net (code "68") (name "unconnected-(CN2-PadDAT1)") (class "Default")
      (node (ref "CN2") (pin "DAT1") (pinfunction "DAT1_DAT1") (pintype "bidirectional"))
    )
    (net (code "69") (name "unconnected-(CN2-PadDAT2)") (class "Default")
      (node (ref "CN2") (pin "DAT2") (pinfunction "DAT2_DAT2") (pintype "bidirectional"))
    )
    (net (code "70") (name "unconnected-(JTAG1-Pad7)") (class "Default")
      (node (ref "JTAG1") (pin "7") (pinfunction "7_7") (pintype "passive"))
    )
    (net (code "71") (name "unconnected-(U$62-LED1{slash}REGOFF-Pad3)") (class "Default")
      (node (ref "U$62") (pin "3") (pinfunction "LED1/REGOFF_3") (pintype "bidirectional"))
    )
    (net (code "72") (name "unconnected-(U1-N.C.-Pad13)") (class "Default")
      (node (ref "U1") (pin "13") (pinfunction "N.C._13") (pintype "no_connect"))
    )
    (net (code "73") (name "unconnected-(U1-P0[0]{slash}RD1{slash}TXD3{slash}SDA1-Pad46)") (class "Default")
      (node (ref "U1") (pin "46") (pinfunction "P0[0]/RD1/TXD3/SDA1_46") (pintype "bidirectional"))
    )
    (net (code "74") (name "unconnected-(U1-P0[1]{slash}TD1{slash}RXD3{slash}SCL1-Pad47)") (class "Default")
      (node (ref "U1") (pin "47") (pinfunction "P0[1]/TD1/RXD3/SCL1_47") (pintype "bidirectional"))
    )
    (net (code "75") (name "unconnected-(U1-P0[2]{slash}TXD0{slash}AD0[7]-Pad98)") (class "Default")
      (node (ref "U1") (pin "98") (pinfunction "P0[2]/TXD0/AD0[7]_98") (pintype "bidirectional"))
    )
    (net (code "76") (name "unconnected-(U1-P0[4]{slash}I2SRX_CLK{slash}RD2{slash}CAP2[0]-Pad81)") (class "Default")
      (node (ref "U1") (pin "81") (pinfunction "P0[4]/I2SRX_CLK/RD2/CAP2[0]_81") (pintype "bidirectional"))
    )
    (net (code "77") (name "unconnected-(U1-P0[10]{slash}TXD2{slash}SDA2{slash}MAT3[0]-Pad48)") (class "Default")
      (node (ref "U1") (pin "48") (pinfunction "P0[10]/TXD2/SDA2/MAT3[0]_48") (pintype "bidirectional"))
    )
    (net (code "78") (name "unconnected-(U1-P0[11]{slash}RXD2{slash}SCL2{slash}MAT3[1]-Pad49)") (class "Default")
      (node (ref "U1") (pin "49") (pinfunction "P0[11]/RXD2/SCL2/MAT3[1]_49") (pintype "bidirectional"))
    )
    (net (code "79") (name "unconnected-(U1-P0[19]{slash}DSR1{slash}SDA1-Pad59)") (class "Default")
      (node (ref "U1") (pin "59") (pinfunction "P0[19]/DSR1/SDA1_59") (pintype "bidirectional"))
    )
    (net (code "80") (name "unconnected-(U1-P0[20]{slash}DTR1{slash}SCL1-Pad58)") (class "Default")
      (node (ref "U1") (pin "58") (pinfunction "P0[20]/DTR1/SCL1_58") (pintype "bidirectional"))
    )
    (net (code "81") (name "unconnected-(U1-P0[21]{slash}RI1{slash}RD1-Pad57)") (class "Default")
      (node (ref "U1") (pin "57") (pinfunction "P0[21]/RI1/RD1_57") (pintype "bidirectional"))
    )
    (net (code "82") (name "unconnected-(U1-P0[22]{slash}RTS1{slash}TD1-Pad56)") (class "Default")
      (node (ref "U1") (pin "56") (pinfunction "P0[22]/RTS1/TD1_56") (pintype "bidirectional"))
    )
    (net (code "83") (name "unconnected-(U1-P0[23]{slash}AD0[0]{slash}I2SRX_CLK{slash}CAP3[0]-Pad9)") (class "Default")
      (node (ref "U1") (pin "9") (pinfunction "P0[23]/AD0[0]/I2SRX_CLK/CAP3[0]_9") (pintype "bidirectional"))
    )
    (net (code "84") (name "unconnected-(U1-P0[24]{slash}AD0[1]{slash}I2SRX_WS{slash}CAP3[1]-Pad8)") (class "Default")
      (node (ref "U1") (pin "8") (pinfunction "P0[24]/AD0[1]/I2SRX_WS/CAP3[1]_8") (pintype "bidirectional"))
    )
    (net (code "85") (name "unconnected-(U1-P0[25]{slash}AD0[2]{slash}I2SRX_SDA{slash}TXD3-Pad7)") (class "Default")
      (node (ref "U1") (pin "7") (pinfunction "P0[25]/AD0[2]/I2SRX_SDA/TXD3_7") (pintype "bidirectional"))
    )
    (net (code "86") (name "unconnected-(U1-P0[26]{slash}AD0[3]{slash}AOUT{slash}RXD3-Pad6)") (class "Default")
      (node (ref "U1") (pin "6") (pinfunction "P0[26]/AD0[3]/AOUT/RXD3_6") (pintype "bidirectional"))
    )
    (net (code "87") (name "unconnected-(U1-P0[29]{slash}USB_D+-Pad29)") (class "Default")
      (node (ref "U1") (pin "29") (pinfunction "P0[29]/USB_D+_29") (pintype "bidirectional"))
    )
    (net (code "88") (name "unconnected-(U1-P0[30]{slash}USB_D--Pad30)") (class "Default")
      (node (ref "U1") (pin "30") (pinfunction "P0[30]/USB_D-_30") (pintype "bidirectional"))
    )
    (net (code "89") (name "unconnected-(U1-P1[18]{slash}USB_UP_LED{slash}PWM1[1]{slash}CAP1[0]-Pad32)") (class "Default")
      (node (ref "U1") (pin "32") (pinfunction "P1[18]/USB_UP_LED/PWM1[1]/CAP1[0]_32") (pintype "bidirectional"))
    )
    (net (code "90") (name "unconnected-(U1-P1[19]{slash}MC0A{slash}USB_PPWR{slash}CAP1[1]-Pad33)") (class "Default")
      (node (ref "U1") (pin "33") (pinfunction "P1[19]/MC0A/USB_PPWR/CAP1[1]_33") (pintype "bidirectional"))
    )
    (net (code "91") (name "unconnected-(U1-P1[20]{slash}MCFB0{slash}PWM1[2]{slash}SCK0-Pad34)") (class "Default")
      (node (ref "U1") (pin "34") (pinfunction "P1[20]/MCFB0/PWM1[2]/SCK0_34") (pintype "bidirectional"))
    )
    (net (code "92") (name "unconnected-(U1-P1[21]{slash}MCABORT{slash}PWM1[3]{slash}SSEL0-Pad35)") (class "Default")
      (node (ref "U1") (pin "35") (pinfunction "P1[21]/MCABORT/PWM1[3]/SSEL0_35") (pintype "bidirectional"))
    )
    (net (code "93") (name "unconnected-(U1-P1[22]{slash}MC0B{slash}USB_PWRD{slash}MAT1[0]-Pad36)") (class "Default")
      (node (ref "U1") (pin "36") (pinfunction "P1[22]/MC0B/USB_PWRD/MAT1[0]_36") (pintype "bidirectional"))
    )
    (net (code "94") (name "unconnected-(U1-P1[23]{slash}MCFB1{slash}PWM1[4]{slash}MISO0-Pad37)") (class "Default")
      (node (ref "U1") (pin "37") (pinfunction "P1[23]/MCFB1/PWM1[4]/MISO0_37") (pintype "bidirectional"))
    )
    (net (code "95") (name "unconnected-(U1-P1[24]{slash}MCFB2{slash}PWM1[5]{slash}MOSI0-Pad38)") (class "Default")
      (node (ref "U1") (pin "38") (pinfunction "P1[24]/MCFB2/PWM1[5]/MOSI0_38") (pintype "bidirectional"))
    )
    (net (code "96") (name "unconnected-(U1-P1[25]{slash}MC1A{slash}MAT1[1]-Pad39)") (class "Default")
      (node (ref "U1") (pin "39") (pinfunction "P1[25]/MC1A/MAT1[1]_39") (pintype "bidirectional"))
    )
    (net (code "97") (name "unconnected-(U1-P1[26]{slash}MC1B{slash}PWM1[6]{slash}CAP0[0]-Pad40)") (class "Default")
      (node (ref "U1") (pin "40") (pinfunction "P1[26]/MC1B/PWM1[6]/CAP0[0]_40") (pintype "bidirectional"))
    )
    (net (code "98") (name "unconnected-(U1-P1[27]{slash}CLKOUT{slash}USB_OVRCR{slash}CAP0[1]-Pad43)") (class "Default")
      (node (ref "U1") (pin "43") (pinfunction "P1[27]/CLKOUT/USB_OVRCR/CAP0[1]_43") (pintype "bidirectional"))
    )
    (net (code "99") (name "unconnected-(U1-P1[28]{slash}MC2A{slash}PCAP1[0]{slash}MAT0[0]-Pad44)") (class "Default")
      (node (ref "U1") (pin "44") (pinfunction "P1[28]/MC2A/PCAP1[0]/MAT0[0]_44") (pintype "bidirectional"))
    )
    (net (code "100") (name "unconnected-(U1-P1[29]{slash}MC2B{slash}PCAP1[1]{slash}MAT0[1]-Pad45)") (class "Default")
      (node (ref "U1") (pin "45") (pinfunction "P1[29]/MC2B/PCAP1[1]/MAT0[1]_45") (pintype "bidirectional"))
    )
    (net (code "101") (name "unconnected-(U1-P1[30]{slash}VBUS{slash}AD0[4]-Pad21)") (class "Default")
      (node (ref "U1") (pin "21") (pinfunction "P1[30]/VBUS/AD0[4]_21") (pintype "bidirectional"))
    )
    (net (code "102") (name "unconnected-(U1-P1[31]{slash}SCK1{slash}AD0[5]-Pad20)") (class "Default")
      (node (ref "U1") (pin "20") (pinfunction "P1[31]/SCK1/AD0[5]_20") (pintype "bidirectional"))
    )
    (net (code "103") (name "unconnected-(U1-P2[4]{slash}PWM1[5]{slash}DSR1{slash}TRACEDATA[1]-Pad69)") (class "Default")
      (node (ref "U1") (pin "69") (pinfunction "P2[4]/PWM1[5]/DSR1/TRACEDATA[1]_69") (pintype "bidirectional"))
    )
    (net (code "104") (name "unconnected-(U1-P2[5]{slash}PWM1[6]{slash}DTR1{slash}TRACEDATA[0]-Pad68)") (class "Default")
      (node (ref "U1") (pin "68") (pinfunction "P2[5]/PWM1[6]/DTR1/TRACEDATA[0]_68") (pintype "bidirectional"))
    )
    (net (code "105") (name "unconnected-(U1-P2[6]{slash}PCAP1[0]{slash}RI1{slash}TRACECLK-Pad67)") (class "Default")
      (node (ref "U1") (pin "67") (pinfunction "P2[6]/PCAP1[0]/RI1/TRACECLK_67") (pintype "bidirectional"))
    )
    (net (code "106") (name "unconnected-(U1-P2[7]{slash}RD2{slash}RTS1-Pad66)") (class "Default")
      (node (ref "U1") (pin "66") (pinfunction "P2[7]/RD2/RTS1_66") (pintype "bidirectional"))
    )
    (net (code "107") (name "unconnected-(U1-P2[8]{slash}TD2{slash}TXD2-Pad65)") (class "Default")
      (node (ref "U1") (pin "65") (pinfunction "P2[8]/TD2/TXD2_65") (pintype "bidirectional"))
    )
    (net (code "108") (name "unconnected-(U1-P2[9]{slash}USB_CONNECT{slash}RXD2-Pad64)") (class "Default")
      (node (ref "U1") (pin "64") (pinfunction "P2[9]/USB_CONNECT/RXD2_64") (pintype "bidirectional"))
    )
    (net (code "109") (name "unconnected-(U1-P2[12]{slash}EINT2{slash}I2STX_WS-Pad51)") (class "Default")
      (node (ref "U1") (pin "51") (pinfunction "P2[12]/EINT2/I2STX_WS_51") (pintype "bidirectional"))
    )
    (net (code "110") (name "unconnected-(U1-P2[13]{slash}EINT3{slash}I2STX_SDA-Pad50)") (class "Default")
      (node (ref "U1") (pin "50") (pinfunction "P2[13]/EINT3/I2STX_SDA_50") (pintype "bidirectional"))
    )
    (net (code "111") (name "unconnected-(U1-P3[25]{slash}MAT0[0]{slash}PWM1[2]-Pad27)") (class "Default")
      (node (ref "U1") (pin "27") (pinfunction "P3[25]/MAT0[0]/PWM1[2]_27") (pintype "bidirectional"))
    )
    (net (code "112") (name "unconnected-(U1-P3[26]{slash}STCLK{slash}MAT0[1]{slash}PWM1[3]-Pad26)") (class "Default")
      (node (ref "U1") (pin "26") (pinfunction "P3[26]/STCLK/MAT0[1]/PWM1[3]_26") (pintype "bidirectional"))
    )
    (net (code "113") (name "unconnected-(U1-P4[28]{slash}RX_MCLK{slash}MAT2[0]{slash}TXD3-Pad82)") (class "Default")
      (node (ref "U1") (pin "82") (pinfunction "P4[28]/RX_MCLK/MAT2[0]/TXD3_82") (pintype "bidirectional"))
    )
    (net (code "114") (name "unconnected-(U1-P4[29]{slash}TX_MCLK{slash}MAT2[1]{slash}RXD3-Pad85)") (class "Default")
      (node (ref "U1") (pin "85") (pinfunction "P4[29]/TX_MCLK/MAT2[1]/RXD3_85") (pintype "bidirectional"))
    )
    (net (code "115") (name "unconnected-(U1-RSTOUT-Pad14)") (class "Default")
      (node (ref "U1") (pin "14") (pinfunction "RSTOUT_14") (pintype "bidirectional"))
    )
    (net (code "116") (name "unconnected-(U1-RTCK-Pad100)") (class "Default")
      (node (ref "U1") (pin "100") (pinfunction "RTCK_100") (pintype "bidirectional"))
    )
    (net (code "117") (name "unconnected-(U1-RTCX1-Pad16)") (class "Default")
      (node (ref "U1") (pin "16") (pinfunction "RTCX1_16") (pintype "bidirectional"))
    )
    (net (code "118") (name "unconnected-(U1-RTCX2-Pad18)") (class "Default")
      (node (ref "U1") (pin "18") (pinfunction "RTCX2_18") (pintype "bidirectional"))
    )
    (net (code "119") (name "unconnected-(U1-XTAL2-Pad23)") (class "Default")
      (node (ref "U1") (pin "23") (pinfunction "XTAL2_23") (pintype "bidirectional"))
    )
    (net (code "120") (name "unconnected-(U8-N.C.-Pad1)") (class "Default")
      (node (ref "U8") (pin "1") (pinfunction "N.C._1") (pintype "no_connect"))
    )
  )
)
